# Peripherals.net
KiCad netlist of a schematic drawn in Altium Designer
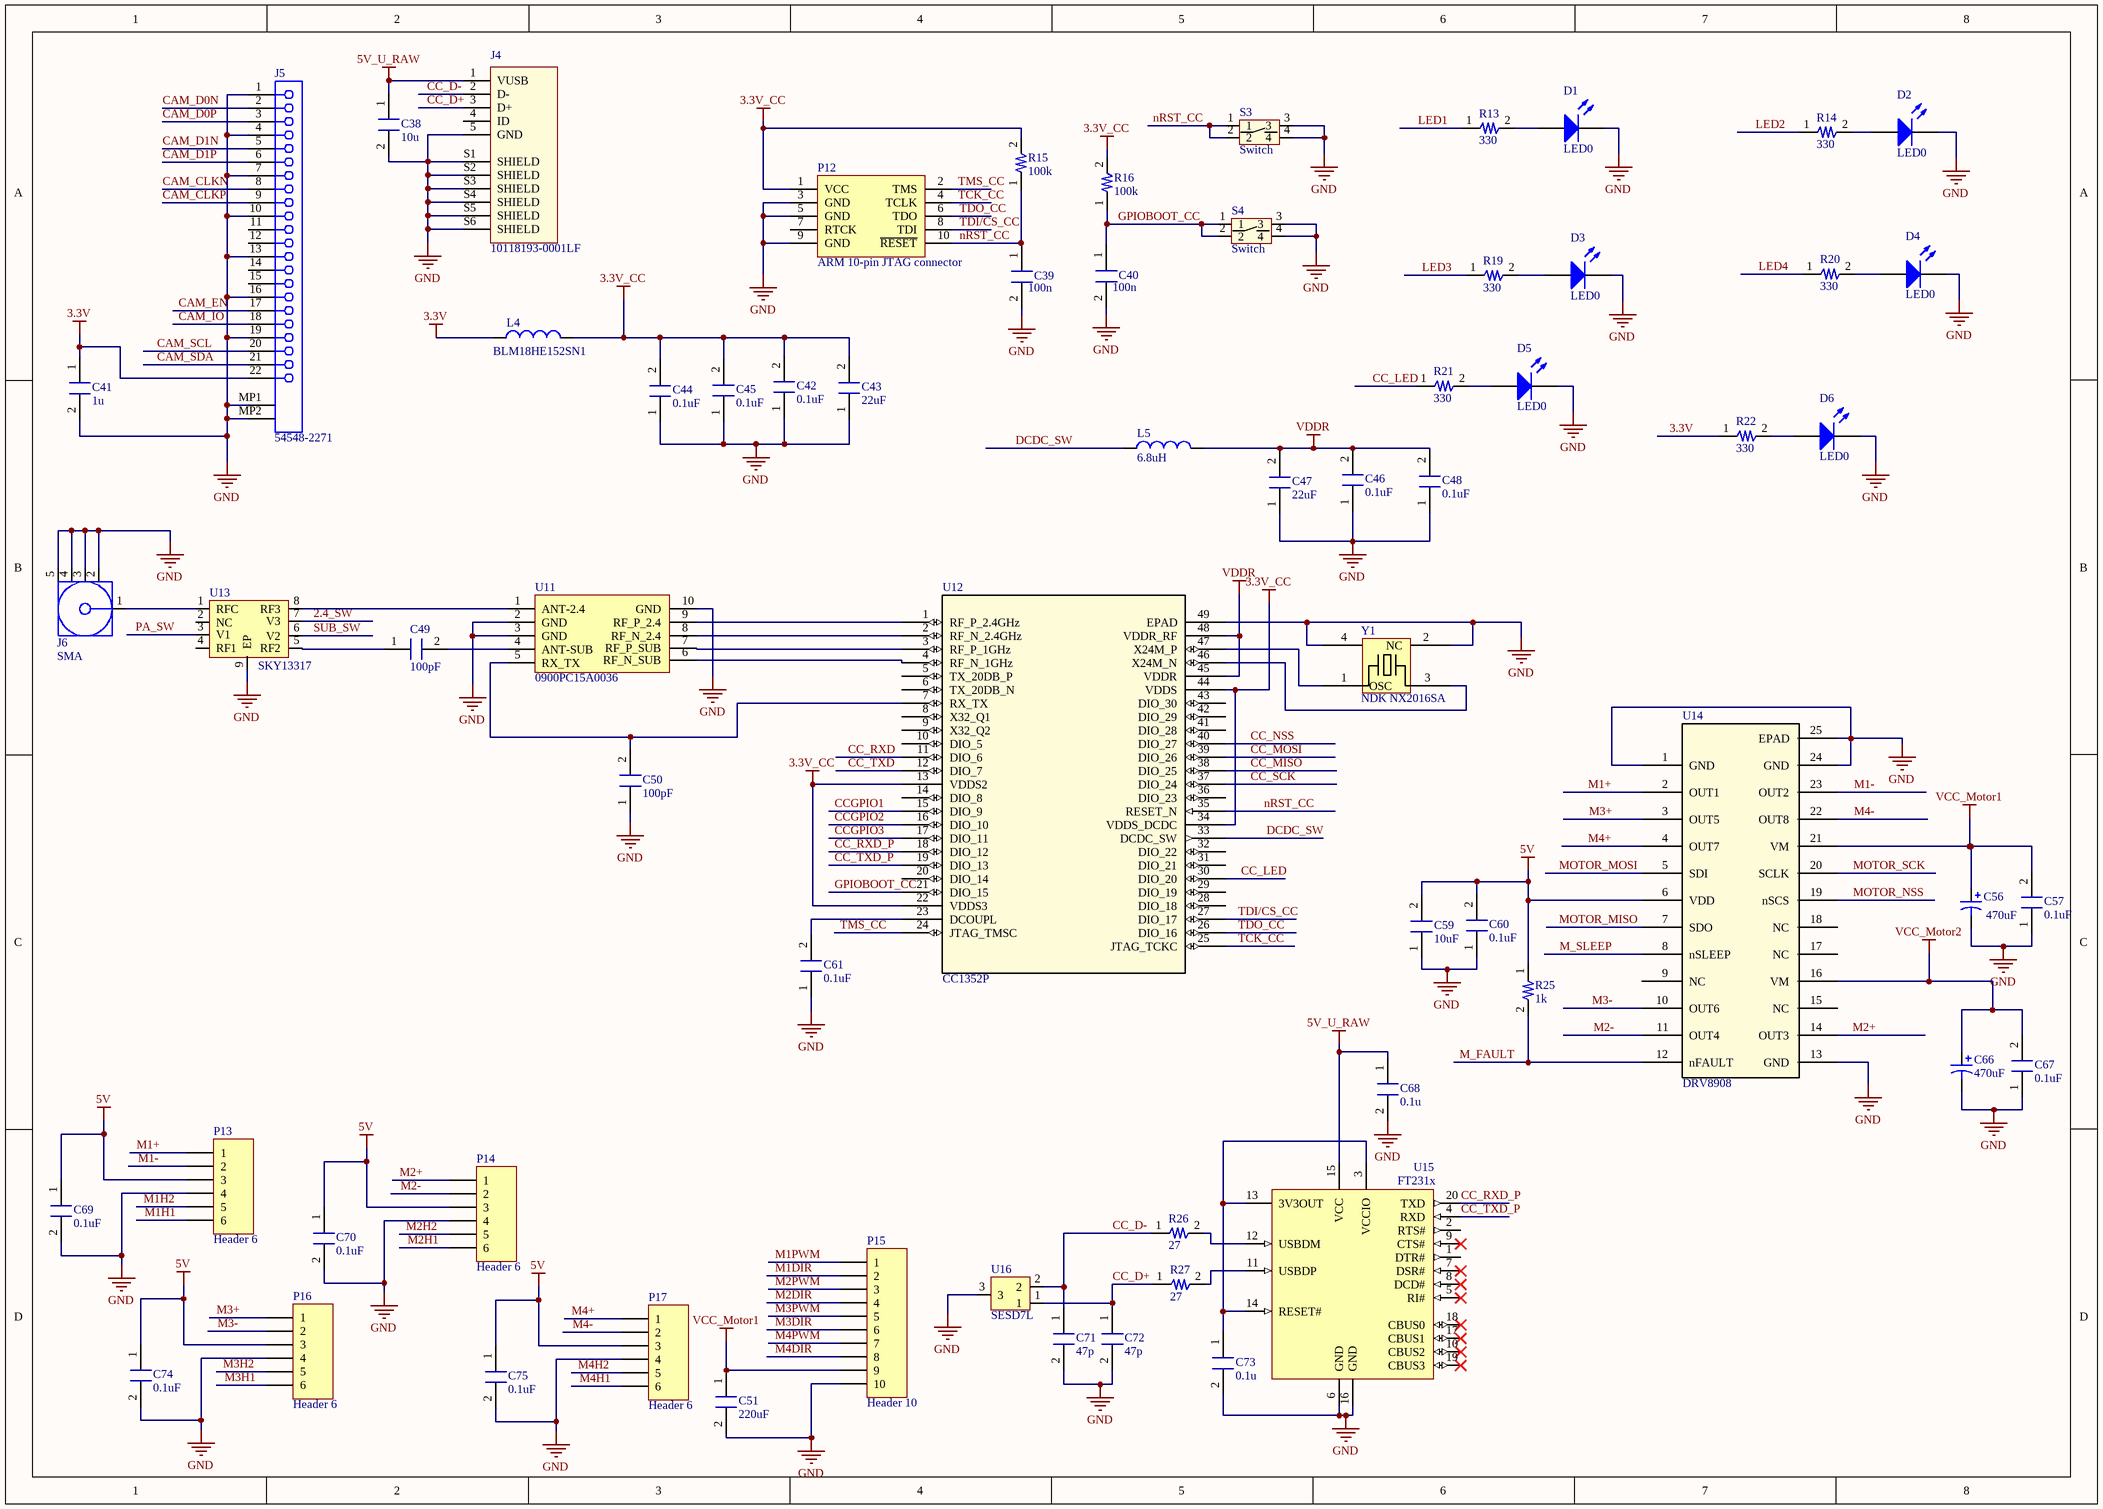
[diagram p0: Peripherals.SchDoc]

(export (version "E")
  (design (tool "Eeschema 10.0.6"))
  (components
    (comp (ref "C38")
      (value "10u")
      (footprint "Capacitor 0603")
      (fields (field (name "Comment") "Ceramic Capacitor"))
      (libsource (lib "Custom") (part "Ceramic Capacitor"))
    )
    (comp (ref "C39")
      (value "100n")
      (footprint "Capacitor 0402")
      (fields (field (name "Comment") "Ceramic Capacitor"))
      (libsource (lib "Custom") (part "Ceramic Capacitor"))
    )
    (comp (ref "C40")
      (value "100n")
      (footprint "Capacitor 0402")
      (fields (field (name "Comment") "Ceramic Capacitor"))
      (libsource (lib "Custom") (part "Ceramic Capacitor"))
    )
    (comp (ref "C41")
      (value "1u")
      (footprint "Capacitor 0402")
      (fields (field (name "Comment") "Ceramic Capacitor"))
      (libsource (lib "Custom") (part "Ceramic Capacitor"))
    )
    (comp (ref "C42")
      (value "0.1uF")
      (footprint "Capacitor 0402")
      (fields (field (name "Comment") "Ceramic Capacitor"))
      (libsource (lib "Custom") (part "Ceramic Capacitor"))
    )
    (comp (ref "C43")
      (value "22uF")
      (footprint "Capacitor 0603")
      (fields (field (name "Comment") "Ceramic Capacitor"))
      (libsource (lib "Custom") (part "Ceramic Capacitor"))
    )
    (comp (ref "C44")
      (value "0.1uF")
      (footprint "Capacitor 0402")
      (fields (field (name "Comment") "Ceramic Capacitor"))
      (libsource (lib "Custom") (part "Ceramic Capacitor"))
    )
    (comp (ref "C45")
      (value "0.1uF")
      (footprint "Capacitor 0402")
      (fields (field (name "Comment") "Ceramic Capacitor"))
      (libsource (lib "Custom") (part "Ceramic Capacitor"))
    )
    (comp (ref "C46")
      (value "0.1uF")
      (footprint "Capacitor 0402")
      (fields (field (name "Comment") "Ceramic Capacitor"))
      (libsource (lib "Custom") (part "Ceramic Capacitor"))
    )
    (comp (ref "C47")
      (value "22uF")
      (footprint "Capacitor 0603")
      (fields (field (name "Comment") "Ceramic Capacitor"))
      (libsource (lib "Custom") (part "Ceramic Capacitor"))
    )
    (comp (ref "C48")
      (value "0.1uF")
      (footprint "Capacitor 0402")
      (fields (field (name "Comment") "Ceramic Capacitor"))
      (libsource (lib "Custom") (part "Ceramic Capacitor"))
    )
    (comp (ref "C49")
      (value "100pF")
      (footprint "Capacitor 0402")
      (fields (field (name "Comment") "Ceramic Capacitor"))
      (libsource (lib "Custom") (part "Ceramic Capacitor"))
    )
    (comp (ref "C50")
      (value "100pF")
      (footprint "Capacitor 0402")
      (fields (field (name "Comment") "Ceramic Capacitor"))
      (libsource (lib "Custom") (part "Ceramic Capacitor"))
    )
    (comp (ref "C51")
      (value "220uF")
      (footprint "CAPAE250P680X1220_VERT")
      (fields (field (name "Comment") "Ceramic Capacitor"))
      (libsource (lib "Custom") (part "Ceramic Capacitor"))
    )
    (comp (ref "C56")
      (value "470uF")
      (footprint "RB7.6-15")
      (description "Polarized Capacitor (Radial)")
      (fields (field (name "PUBLISHER") "Altium Limited"))
      (libsource (lib "Miscellaneous Devices") (part "Cap Pol1"))
    )
    (comp (ref "C57")
      (value "0.1uF")
      (footprint "Capacitor 0402")
      (fields (field (name "Comment") "Ceramic Capacitor"))
      (libsource (lib "Custom") (part "Ceramic Capacitor"))
    )
    (comp (ref "C59")
      (value "10uF")
      (footprint "Capacitor 0603")
      (fields (field (name "Comment") "Ceramic Capacitor"))
      (libsource (lib "Custom") (part "Ceramic Capacitor"))
    )
    (comp (ref "C60")
      (value "0.1uF")
      (footprint "Capacitor 0402")
      (fields (field (name "Comment") "Ceramic Capacitor"))
      (libsource (lib "Custom") (part "Ceramic Capacitor"))
    )
    (comp (ref "C61")
      (value "0.1uF")
      (footprint "Capacitor 0402")
      (fields (field (name "Comment") "Ceramic Capacitor"))
      (libsource (lib "Custom") (part "Ceramic Capacitor"))
    )
    (comp (ref "C66")
      (value "470uF")
      (footprint "RB7.6-15")
      (description "Polarized Capacitor (Radial)")
      (fields (field (name "PUBLISHER") "Altium Limited"))
      (libsource (lib "Miscellaneous Devices") (part "Cap Pol1"))
    )
    (comp (ref "C67")
      (value "0.1uF")
      (footprint "Capacitor 0402")
      (fields (field (name "Comment") "Ceramic Capacitor"))
      (libsource (lib "Custom") (part "Ceramic Capacitor"))
    )
    (comp (ref "C68")
      (value "0.1u")
      (footprint "Capacitor 0402")
      (fields (field (name "Comment") "Ceramic Capacitor"))
      (libsource (lib "Custom") (part "Ceramic Capacitor"))
    )
    (comp (ref "C69")
      (value "0.1uF")
      (footprint "Capacitor 0402")
      (fields (field (name "Comment") "Ceramic Capacitor"))
      (libsource (lib "Custom") (part "Ceramic Capacitor"))
    )
    (comp (ref "C70")
      (value "0.1uF")
      (footprint "Capacitor 0402")
      (fields (field (name "Comment") "Ceramic Capacitor"))
      (libsource (lib "Custom") (part "Ceramic Capacitor"))
    )
    (comp (ref "C71")
      (value "47p")
      (footprint "Capacitor 0402")
      (fields (field (name "Comment") "Ceramic Capacitor"))
      (libsource (lib "Custom") (part "Ceramic Capacitor"))
    )
    (comp (ref "C72")
      (value "47p")
      (footprint "Capacitor 0402")
      (fields (field (name "Comment") "Ceramic Capacitor"))
      (libsource (lib "Custom") (part "Ceramic Capacitor"))
    )
    (comp (ref "C73")
      (value "0.1u")
      (footprint "Capacitor 0402")
      (fields (field (name "Comment") "Ceramic Capacitor"))
      (libsource (lib "Custom") (part "Ceramic Capacitor"))
    )
    (comp (ref "C74")
      (value "0.1uF")
      (footprint "Capacitor 0402")
      (fields (field (name "Comment") "Ceramic Capacitor"))
      (libsource (lib "Custom") (part "Ceramic Capacitor"))
    )
    (comp (ref "C75")
      (value "0.1uF")
      (footprint "Capacitor 0402")
      (fields (field (name "Comment") "Ceramic Capacitor"))
      (libsource (lib "Custom") (part "Ceramic Capacitor"))
    )
    (comp (ref "D1")
      (value "LED0")
      (footprint "HDR1X2")
      (description "Typical INFRARED GaAs LED")
      (fields (field (name "PUBLISHER") "Altium Limited"))
      (libsource (lib "Miscellaneous Devices") (part "LED0"))
    )
    (comp (ref "D2")
      (value "LED0")
      (footprint "HDR1X2")
      (description "Typical INFRARED GaAs LED")
      (fields (field (name "PUBLISHER") "Altium Limited"))
      (libsource (lib "Miscellaneous Devices") (part "LED0"))
    )
    (comp (ref "D3")
      (value "LED0")
      (footprint "HDR1X2")
      (description "Typical INFRARED GaAs LED")
      (fields (field (name "PUBLISHER") "Altium Limited"))
      (libsource (lib "Miscellaneous Devices") (part "LED0"))
    )
    (comp (ref "D4")
      (value "LED0")
      (footprint "HDR1X2")
      (description "Typical INFRARED GaAs LED")
      (fields (field (name "PUBLISHER") "Altium Limited"))
      (libsource (lib "Miscellaneous Devices") (part "LED0"))
    )
    (comp (ref "D5")
      (value "LED0")
      (footprint "HDR1X2")
      (description "Typical INFRARED GaAs LED")
      (fields (field (name "PUBLISHER") "Altium Limited"))
      (libsource (lib "Miscellaneous Devices") (part "LED0"))
    )
    (comp (ref "D6")
      (value "LED0")
      (footprint "HDR1X2")
      (description "Typical INFRARED GaAs LED")
      (fields (field (name "PUBLISHER") "Altium Limited"))
      (libsource (lib "Miscellaneous Devices") (part "LED0"))
    )
    (comp (ref "J4")
      (value "10118193-0001LF")
      (footprint "FCI_10118193-0001LF_10118193-0001LF(Primary)")
      (description "USB mini")
      (libsource (lib "Custom") (part "USB mini 10118193-0001LF"))
    )
    (comp (ref "J5")
      (value "54548-2271")
      (footprint "54548-2271")
      (libsource (lib "Custom") (part "54548-2271"))
    )
    (comp (ref "J6")
      (value "SMA")
      (footprint "SMA4.75V5A - Straight")
      (libsource (lib "Custom") (part "SMA"))
    )
    (comp (ref "L4")
      (value "BLM18HE152SN1")
      (footprint "Resistor 0603")
      (description "Inductor")
      (libsource (lib "Custom") (part "Inductor"))
    )
    (comp (ref "L5")
      (value "6.8uH")
      (footprint "B82144F2682K000")
      (description "Inductor")
      (fields (field (name "PART NUMBER") "B82144F2682K000"))
      (libsource (lib "Custom") (part "Inductor"))
    )
    (comp (ref "P12")
      (value "ARM 10-pin JTAG connector")
      (footprint "MHDR2X5")
      (description "ARM JTAG/SWD connector")
      (libsource (lib "Custom") (part "ARM JTAG"))
    )
    (comp (ref "P13")
      (value "Header 6")
      (footprint "HDR1X6")
      (description "Header, 6-Pin")
      (fields (field (name "PUBLISHER") "Altium Limited"))
      (libsource (lib "Miscellaneous Connectors") (part "Header 6"))
    )
    (comp (ref "P14")
      (value "Header 6")
      (footprint "HDR1X6")
      (description "Header, 6-Pin")
      (fields (field (name "PUBLISHER") "Altium Limited"))
      (libsource (lib "Miscellaneous Connectors") (part "Header 6"))
    )
    (comp (ref "P15")
      (value "Header 10")
      (footprint "HDR1X10")
      (description "Header, 10-Pin")
      (fields (field (name "PUBLISHER") "Altium Limited"))
      (libsource (lib "Miscellaneous Connectors") (part "Header 10"))
    )
    (comp (ref "P16")
      (value "Header 6")
      (footprint "HDR1X6")
      (description "Header, 6-Pin")
      (fields (field (name "PUBLISHER") "Altium Limited"))
      (libsource (lib "Miscellaneous Connectors") (part "Header 6"))
    )
    (comp (ref "P17")
      (value "Header 6")
      (footprint "HDR1X6")
      (description "Header, 6-Pin")
      (fields (field (name "PUBLISHER") "Altium Limited"))
      (libsource (lib "Miscellaneous Connectors") (part "Header 6"))
    )
    (comp (ref "R13")
      (value "330")
      (footprint "Resistor 0402")
      (description "General Purpose Resistor")
      (fields (field (name "Comment") "Resistor"))
      (libsource (lib "Custom") (part "Resistor"))
    )
    (comp (ref "R14")
      (value "330")
      (footprint "Resistor 0402")
      (description "General Purpose Resistor")
      (fields (field (name "Comment") "Resistor"))
      (libsource (lib "Custom") (part "Resistor"))
    )
    (comp (ref "R15")
      (value "100k")
      (footprint "Resistor 0402")
      (description "General Purpose Resistor")
      (fields (field (name "Comment") "Resistor"))
      (libsource (lib "Custom") (part "Resistor"))
    )
    (comp (ref "R16")
      (value "100k")
      (footprint "Resistor 0402")
      (description "General Purpose Resistor")
      (fields (field (name "Comment") "Resistor"))
      (libsource (lib "Custom") (part "Resistor"))
    )
    (comp (ref "R19")
      (value "330")
      (footprint "Resistor 0402")
      (description "General Purpose Resistor")
      (fields (field (name "Comment") "Resistor"))
      (libsource (lib "Custom") (part "Resistor"))
    )
    (comp (ref "R20")
      (value "330")
      (footprint "Resistor 0402")
      (description "General Purpose Resistor")
      (fields (field (name "Comment") "Resistor"))
      (libsource (lib "Custom") (part "Resistor"))
    )
    (comp (ref "R21")
      (value "330")
      (footprint "Resistor 0402")
      (description "General Purpose Resistor")
      (fields (field (name "Comment") "Resistor"))
      (libsource (lib "Custom") (part "Resistor"))
    )
    (comp (ref "R22")
      (value "330")
      (footprint "Resistor 0402")
      (description "General Purpose Resistor")
      (fields (field (name "Comment") "Resistor"))
      (libsource (lib "Custom") (part "Resistor"))
    )
    (comp (ref "R25")
      (value "1k")
      (footprint "Resistor 0402")
      (description "General Purpose Resistor")
      (fields (field (name "Comment") "Resistor"))
      (libsource (lib "Custom") (part "Resistor"))
    )
    (comp (ref "R26")
      (value "27")
      (footprint "Resistor 0402")
      (description "General Purpose Resistor")
      (fields (field (name "Comment") "Resistor"))
      (libsource (lib "Custom") (part "Resistor"))
    )
    (comp (ref "R27")
      (value "27")
      (footprint "Resistor 0402")
      (description "General Purpose Resistor")
      (fields (field (name "Comment") "Resistor"))
      (libsource (lib "Custom") (part "Resistor"))
    )
    (comp (ref "S3") (value "Switch") (footprint "Switch") (libsource (lib "Custom") (part "Switch")))
    (comp (ref "S4") (value "Switch") (footprint "Switch") (libsource (lib "Custom") (part "Switch")))
    (comp (ref "U11")
      (value "0900PC15A0036")
      (footprint "0900PC15A0036")
      (libsource (lib "Custom") (part "0900PC15A0036"))
    )
    (comp (ref "U12")
      (value "CC1352P")
      (footprint "RGZ48")
      (description "No Description Available")
      (libsource (lib "Custom") (part "CC1352P"))
    )
    (comp (ref "U13") (value "SKY13317") (footprint "DFN-8_DC") (libsource (lib "Custom") (part "SKY13317")))
    (comp (ref "U14")
      (value "DRV8908")
      (footprint "HTTSOP 24")
      (description "No Description Available")
      (libsource (lib "Custom") (part "DRV8908"))
    )
    (comp (ref "U15") (value "FT231x") (footprint "SSOP-20_N") (libsource (lib "Custom") (part "FT231x")))
    (comp (ref "U16")
      (value "SESD7L")
      (footprint "SOT-723")
      (description "TVS Diode - USB")
      (libsource (lib "Custom") (part "SESD7L"))
    )
    (comp (ref "Y1")
      (value "NDK NX2016SA")
      (footprint "NDK NX2016SA")
      (libsource (lib "Custom") (part "NDK NX2016SA"))
    )
  )
  (nets
    (net (code "1") (name "/2.4_SW") (class "Default")
      (node (ref "U13") (pin "7") (pinfunction "V3_7") (pintype "passive"))
    )
    (net (code "2") (name "/CAM_CLKN") (class "Default")
      (node (ref "J5") (pin "8") (pinfunction "8_8") (pintype "passive"))
    )
    (net (code "3") (name "/CAM_CLKP") (class "Default")
      (node (ref "J5") (pin "9") (pinfunction "9_9") (pintype "passive"))
    )
    (net (code "4") (name "/CAM_D0N") (class "Default")
      (node (ref "J5") (pin "2") (pinfunction "2_2") (pintype "passive"))
    )
    (net (code "5") (name "/CAM_D0P") (class "Default")
      (node (ref "J5") (pin "3") (pinfunction "3_3") (pintype "passive"))
    )
    (net (code "6") (name "/CAM_D1N") (class "Default")
      (node (ref "J5") (pin "5") (pinfunction "5_5") (pintype "passive"))
    )
    (net (code "7") (name "/CAM_D1P") (class "Default")
      (node (ref "J5") (pin "6") (pinfunction "6_6") (pintype "passive"))
    )
    (net (code "8") (name "/CAM_EN") (class "Default")
      (node (ref "J5") (pin "17") (pinfunction "17_17") (pintype "passive"))
    )
    (net (code "9") (name "/CAM_IO") (class "Default")
      (node (ref "J5") (pin "18") (pinfunction "18_18") (pintype "passive"))
    )
    (net (code "10") (name "/CAM_SCL") (class "Default")
      (node (ref "J5") (pin "20") (pinfunction "20_20") (pintype "passive"))
    )
    (net (code "11") (name "/CAM_SDA") (class "Default")
      (node (ref "J5") (pin "21") (pinfunction "21_21") (pintype "passive"))
    )
    (net (code "12") (name "/CCGPIO1") (class "Default")
      (node (ref "U12") (pin "15") (pinfunction "DIO_9_15") (pintype "bidirectional"))
    )
    (net (code "13") (name "/CCGPIO2") (class "Default")
      (node (ref "U12") (pin "16") (pinfunction "DIO_10_16") (pintype "bidirectional"))
    )
    (net (code "14") (name "/CCGPIO3") (class "Default")
      (node (ref "U12") (pin "17") (pinfunction "DIO_11_17") (pintype "bidirectional"))
    )
    (net (code "15") (name "/CC_D+") (class "Default")
      (node (ref "C72") (pin "1") (pinfunction "1_1") (pintype "passive"))
      (node (ref "J4") (pin "3") (pinfunction "D+_3") (pintype "passive"))
      (node (ref "R27") (pin "1") (pinfunction "1_1") (pintype "passive"))
      (node (ref "U16") (pin "1") (pinfunction "1_1") (pintype "passive"))
    )
    (net (code "16") (name "/CC_D-") (class "Default")
      (node (ref "C71") (pin "1") (pinfunction "1_1") (pintype "passive"))
      (node (ref "J4") (pin "2") (pinfunction "D-_2") (pintype "passive"))
      (node (ref "R26") (pin "1") (pinfunction "1_1") (pintype "passive"))
      (node (ref "U16") (pin "2") (pinfunction "2_2") (pintype "passive"))
    )
    (net (code "17") (name "/CC_LED") (class "Default")
      (node (ref "R21") (pin "1") (pinfunction "1_1") (pintype "passive"))
      (node (ref "U12") (pin "30") (pinfunction "DIO_20_30") (pintype "bidirectional"))
    )
    (net (code "18") (name "/CC_MISO") (class "Default")
      (node (ref "U12") (pin "38") (pinfunction "DIO_25_38") (pintype "bidirectional"))
    )
    (net (code "19") (name "/CC_MOSI") (class "Default")
      (node (ref "U12") (pin "39") (pinfunction "DIO_26_39") (pintype "bidirectional"))
    )
    (net (code "20") (name "/CC_NSS") (class "Default")
      (node (ref "U12") (pin "40") (pinfunction "DIO_27_40") (pintype "bidirectional"))
    )
    (net (code "21") (name "/CC_RXD") (class "Default")
      (node (ref "U12") (pin "11") (pinfunction "DIO_6_11") (pintype "bidirectional"))
    )
    (net (code "22") (name "/CC_RXD_P") (class "Default")
      (node (ref "U12") (pin "18") (pinfunction "DIO_12_18") (pintype "bidirectional"))
      (node (ref "U15") (pin "20") (pinfunction "TXD_20") (pintype "output"))
    )
    (net (code "23") (name "/CC_SCK") (class "Default")
      (node (ref "U12") (pin "37") (pinfunction "DIO_24_37") (pintype "bidirectional"))
    )
    (net (code "24") (name "/CC_TXD") (class "Default")
      (node (ref "U12") (pin "12") (pinfunction "DIO_7_12") (pintype "bidirectional"))
    )
    (net (code "25") (name "/CC_TXD_P") (class "Default")
      (node (ref "U12") (pin "19") (pinfunction "DIO_13_19") (pintype "bidirectional"))
      (node (ref "U15") (pin "4") (pinfunction "RXD_4") (pintype "input"))
    )
    (net (code "26") (name "/DCDC_SW") (class "Default")
      (node (ref "L5") (pin "1") (pinfunction "1_1") (pintype "passive"))
      (node (ref "U12") (pin "33") (pinfunction "DCDC_SW_33") (pintype "output"))
    )
    (net (code "27") (name "/GPIOBOOT_CC") (class "Default")
      (node (ref "C40") (pin "1") (pinfunction "1_1") (pintype "passive"))
      (node (ref "R16") (pin "1") (pinfunction "1_1") (pintype "passive"))
      (node (ref "S4") (pin "1") (pinfunction "1_1") (pintype "passive"))
      (node (ref "S4") (pin "2") (pinfunction "2_2") (pintype "passive"))
      (node (ref "U12") (pin "21") (pinfunction "DIO_15_21") (pintype "bidirectional"))
    )
    (net (code "28") (name "/LED1") (class "Default")
      (node (ref "R13") (pin "1") (pinfunction "1_1") (pintype "passive"))
    )
    (net (code "29") (name "/LED2") (class "Default")
      (node (ref "R14") (pin "1") (pinfunction "1_1") (pintype "passive"))
    )
    (net (code "30") (name "/LED3") (class "Default")
      (node (ref "R19") (pin "1") (pinfunction "1_1") (pintype "passive"))
    )
    (net (code "31") (name "/LED4") (class "Default")
      (node (ref "R20") (pin "1") (pinfunction "1_1") (pintype "passive"))
    )
    (net (code "32") (name "/M1+") (class "Default")
      (node (ref "P13") (pin "1") (pinfunction "1_1") (pintype "passive"))
      (node (ref "U14") (pin "2") (pinfunction "OUT1_2") (pintype "passive"))
    )
    (net (code "33") (name "/M1-") (class "Default")
      (node (ref "P13") (pin "2") (pinfunction "2_2") (pintype "passive"))
      (node (ref "U14") (pin "23") (pinfunction "OUT2_23") (pintype "passive"))
    )
    (net (code "34") (name "/M1DIR") (class "Default")
      (node (ref "P15") (pin "2") (pinfunction "2_2") (pintype "passive"))
    )
    (net (code "35") (name "/M1H1") (class "Default")
      (node (ref "P13") (pin "6") (pinfunction "6_6") (pintype "passive"))
    )
    (net (code "36") (name "/M1H2") (class "Default")
      (node (ref "P13") (pin "5") (pinfunction "5_5") (pintype "passive"))
    )
    (net (code "37") (name "/M1PWM") (class "Default")
      (node (ref "P15") (pin "1") (pinfunction "1_1") (pintype "passive"))
    )
    (net (code "38") (name "/M2+") (class "Default")
      (node (ref "P14") (pin "1") (pinfunction "1_1") (pintype "passive"))
      (node (ref "U14") (pin "14") (pinfunction "OUT3_14") (pintype "passive"))
    )
    (net (code "39") (name "/M2-") (class "Default")
      (node (ref "P14") (pin "2") (pinfunction "2_2") (pintype "passive"))
      (node (ref "U14") (pin "11") (pinfunction "OUT4_11") (pintype "passive"))
    )
    (net (code "40") (name "/M2DIR") (class "Default")
      (node (ref "P15") (pin "4") (pinfunction "4_4") (pintype "passive"))
    )
    (net (code "41") (name "/M2H1") (class "Default")
      (node (ref "P14") (pin "6") (pinfunction "6_6") (pintype "passive"))
    )
    (net (code "42") (name "/M2H2") (class "Default")
      (node (ref "P14") (pin "5") (pinfunction "5_5") (pintype "passive"))
    )
    (net (code "43") (name "/M2PWM") (class "Default")
      (node (ref "P15") (pin "3") (pinfunction "3_3") (pintype "passive"))
    )
    (net (code "44") (name "/M3+") (class "Default")
      (node (ref "P16") (pin "1") (pinfunction "1_1") (pintype "passive"))
      (node (ref "U14") (pin "3") (pinfunction "OUT5_3") (pintype "passive"))
    )
    (net (code "45") (name "/M3-") (class "Default")
      (node (ref "P16") (pin "2") (pinfunction "2_2") (pintype "passive"))
      (node (ref "U14") (pin "10") (pinfunction "OUT6_10") (pintype "passive"))
    )
    (net (code "46") (name "/M3DIR") (class "Default")
      (node (ref "P15") (pin "6") (pinfunction "6_6") (pintype "passive"))
    )
    (net (code "47") (name "/M3H1") (class "Default")
      (node (ref "P16") (pin "6") (pinfunction "6_6") (pintype "passive"))
    )
    (net (code "48") (name "/M3H2") (class "Default")
      (node (ref "P16") (pin "5") (pinfunction "5_5") (pintype "passive"))
    )
    (net (code "49") (name "/M3PWM") (class "Default")
      (node (ref "P15") (pin "5") (pinfunction "5_5") (pintype "passive"))
    )
    (net (code "50") (name "/M4+") (class "Default")
      (node (ref "P17") (pin "1") (pinfunction "1_1") (pintype "passive"))
      (node (ref "U14") (pin "4") (pinfunction "OUT7_4") (pintype "passive"))
    )
    (net (code "51") (name "/M4-") (class "Default")
      (node (ref "P17") (pin "2") (pinfunction "2_2") (pintype "passive"))
      (node (ref "U14") (pin "22") (pinfunction "OUT8_22") (pintype "passive"))
    )
    (net (code "52") (name "/M4DIR") (class "Default")
      (node (ref "P15") (pin "8") (pinfunction "8_8") (pintype "passive"))
    )
    (net (code "53") (name "/M4H1") (class "Default")
      (node (ref "P17") (pin "6") (pinfunction "6_6") (pintype "passive"))
    )
    (net (code "54") (name "/M4H2") (class "Default")
      (node (ref "P17") (pin "5") (pinfunction "5_5") (pintype "passive"))
    )
    (net (code "55") (name "/M4PWM") (class "Default")
      (node (ref "P15") (pin "7") (pinfunction "7_7") (pintype "passive"))
    )
    (net (code "56") (name "/MOTOR_MISO") (class "Default")
      (node (ref "U14") (pin "7") (pinfunction "SDO_7") (pintype "passive"))
    )
    (net (code "57") (name "/MOTOR_MOSI") (class "Default")
      (node (ref "U14") (pin "5") (pinfunction "SDI_5") (pintype "passive"))
    )
    (net (code "58") (name "/MOTOR_NSS") (class "Default")
      (node (ref "U14") (pin "19") (pinfunction "nSCS_19") (pintype "passive"))
    )
    (net (code "59") (name "/MOTOR_SCK") (class "Default")
      (node (ref "U14") (pin "20") (pinfunction "SCLK_20") (pintype "passive"))
    )
    (net (code "60") (name "/M_FAULT") (class "Default")
      (node (ref "R25") (pin "2") (pinfunction "2_2") (pintype "passive"))
      (node (ref "U14") (pin "12") (pinfunction "nFAULT_12") (pintype "passive"))
    )
    (net (code "61") (name "/M_SLEEP") (class "Default")
      (node (ref "U14") (pin "8") (pinfunction "nSLEEP_8") (pintype "passive"))
    )
    (net (code "62") (name "/PA_SW") (class "Default")
      (node (ref "U13") (pin "3") (pinfunction "V1_3") (pintype "passive"))
    )
    (net (code "63") (name "/SUB_SW") (class "Default")
      (node (ref "U13") (pin "6") (pinfunction "V2_6") (pintype "passive"))
    )
    (net (code "64") (name "/TCK_CC") (class "Default")
      (node (ref "P12") (pin "4") (pinfunction "TCLK_4") (pintype "passive"))
      (node (ref "U12") (pin "25") (pinfunction "JTAG_TCKC_25") (pintype "bidirectional"))
    )
    (net (code "65") (name "/TDI{slash}CS_CC") (class "Default")
      (node (ref "P12") (pin "8") (pinfunction "TDI_8") (pintype "passive"))
      (node (ref "U12") (pin "27") (pinfunction "DIO_17_27") (pintype "bidirectional"))
    )
    (net (code "66") (name "/TDO_CC") (class "Default")
      (node (ref "P12") (pin "6") (pinfunction "TDO_6") (pintype "passive"))
      (node (ref "U12") (pin "26") (pinfunction "DIO_16_26") (pintype "bidirectional"))
    )
    (net (code "67") (name "/TMS_CC") (class "Default")
      (node (ref "P12") (pin "2") (pinfunction "TMS_2") (pintype "passive"))
      (node (ref "U12") (pin "24") (pinfunction "JTAG_TMSC_24") (pintype "bidirectional"))
    )
    (net (code "68") (name "/nRST_CC") (class "Default")
      (node (ref "C39") (pin "1") (pinfunction "1_1") (pintype "passive"))
      (node (ref "P12") (pin "10") (pinfunction "~{RESET}_10") (pintype "passive"))
      (node (ref "R15") (pin "1") (pinfunction "1_1") (pintype "passive"))
      (node (ref "S3") (pin "1") (pinfunction "1_1") (pintype "passive"))
      (node (ref "S3") (pin "2") (pinfunction "2_2") (pintype "passive"))
      (node (ref "U12") (pin "35") (pinfunction "RESET_N_35") (pintype "input"))
    )
    (net (code "69") (name "3.3V") (class "Default")
      (node (ref "C41") (pin "1") (pinfunction "1_1") (pintype "passive"))
      (node (ref "J5") (pin "22") (pinfunction "22_22") (pintype "passive"))
      (node (ref "L4") (pin "1") (pinfunction "1_1") (pintype "passive"))
      (node (ref "R22") (pin "1") (pinfunction "1_1") (pintype "passive"))
    )
    (net (code "70") (name "3.3V_CC") (class "Default")
      (node (ref "C42") (pin "2") (pinfunction "2_2") (pintype "passive"))
      (node (ref "C43") (pin "2") (pinfunction "2_2") (pintype "passive"))
      (node (ref "C44") (pin "2") (pinfunction "2_2") (pintype "passive"))
      (node (ref "C45") (pin "2") (pinfunction "2_2") (pintype "passive"))
      (node (ref "L4") (pin "2") (pinfunction "2_2") (pintype "passive"))
      (node (ref "P12") (pin "1") (pinfunction "VCC_1") (pintype "passive"))
      (node (ref "R15") (pin "2") (pinfunction "2_2") (pintype "passive"))
      (node (ref "R16") (pin "2") (pinfunction "2_2") (pintype "passive"))
      (node (ref "U12") (pin "13") (pinfunction "VDDS2_13") (pintype "power_in"))
      (node (ref "U12") (pin "22") (pinfunction "VDDS3_22") (pintype "power_in"))
      (node (ref "U12") (pin "34") (pinfunction "VDDS_DCDC_34") (pintype "power_in"))
      (node (ref "U12") (pin "44") (pinfunction "VDDS_44") (pintype "power_in"))
    )
    (net (code "71") (name "5V") (class "Default")
      (node (ref "C59") (pin "2") (pinfunction "2_2") (pintype "passive"))
      (node (ref "C60") (pin "2") (pinfunction "2_2") (pintype "passive"))
      (node (ref "C69") (pin "1") (pinfunction "1_1") (pintype "passive"))
      (node (ref "C70") (pin "1") (pinfunction "1_1") (pintype "passive"))
      (node (ref "C74") (pin "1") (pinfunction "1_1") (pintype "passive"))
      (node (ref "C75") (pin "1") (pinfunction "1_1") (pintype "passive"))
      (node (ref "P13") (pin "3") (pinfunction "3_3") (pintype "passive"))
      (node (ref "P14") (pin "3") (pinfunction "3_3") (pintype "passive"))
      (node (ref "P16") (pin "3") (pinfunction "3_3") (pintype "passive"))
      (node (ref "P17") (pin "3") (pinfunction "3_3") (pintype "passive"))
      (node (ref "R25") (pin "1") (pinfunction "1_1") (pintype "passive"))
      (node (ref "U14") (pin "6") (pinfunction "VDD_6") (pintype "passive"))
    )
    (net (code "72") (name "5V_U_RAW") (class "Default")
      (node (ref "C38") (pin "1") (pinfunction "1_1") (pintype "passive"))
      (node (ref "C68") (pin "1") (pinfunction "1_1") (pintype "passive"))
      (node (ref "J4") (pin "1") (pinfunction "VUSB_1") (pintype "passive"))
      (node (ref "U15") (pin "15") (pinfunction "VCC_15") (pintype "power_in"))
    )
    (net (code "73") (name "GND") (class "Default")
      (node (ref "C38") (pin "2") (pinfunction "2_2") (pintype "passive"))
      (node (ref "C39") (pin "2") (pinfunction "2_2") (pintype "passive"))
      (node (ref "C40") (pin "2") (pinfunction "2_2") (pintype "passive"))
      (node (ref "C41") (pin "2") (pinfunction "2_2") (pintype "passive"))
      (node (ref "C42") (pin "1") (pinfunction "1_1") (pintype "passive"))
      (node (ref "C43") (pin "1") (pinfunction "1_1") (pintype "passive"))
      (node (ref "C44") (pin "1") (pinfunction "1_1") (pintype "passive"))
      (node (ref "C45") (pin "1") (pinfunction "1_1") (pintype "passive"))
      (node (ref "C46") (pin "1") (pinfunction "1_1") (pintype "passive"))
      (node (ref "C47") (pin "1") (pinfunction "1_1") (pintype "passive"))
      (node (ref "C48") (pin "1") (pinfunction "1_1") (pintype "passive"))
      (node (ref "C50") (pin "1") (pinfunction "1_1") (pintype "passive"))
      (node (ref "C51") (pin "2") (pinfunction "2_2") (pintype "passive"))
      (node (ref "C56") (pin "2") (pinfunction "2_2") (pintype "passive"))
      (node (ref "C57") (pin "1") (pinfunction "1_1") (pintype "passive"))
      (node (ref "C59") (pin "1") (pinfunction "1_1") (pintype "passive"))
      (node (ref "C60") (pin "1") (pinfunction "1_1") (pintype "passive"))
      (node (ref "C61") (pin "1") (pinfunction "1_1") (pintype "passive"))
      (node (ref "C66") (pin "2") (pinfunction "2_2") (pintype "passive"))
      (node (ref "C67") (pin "1") (pinfunction "1_1") (pintype "passive"))
      (node (ref "C68") (pin "2") (pinfunction "2_2") (pintype "passive"))
      (node (ref "C69") (pin "2") (pinfunction "2_2") (pintype "passive"))
      (node (ref "C70") (pin "2") (pinfunction "2_2") (pintype "passive"))
      (node (ref "C71") (pin "2") (pinfunction "2_2") (pintype "passive"))
      (node (ref "C72") (pin "2") (pinfunction "2_2") (pintype "passive"))
      (node (ref "C73") (pin "2") (pinfunction "2_2") (pintype "passive"))
      (node (ref "C74") (pin "2") (pinfunction "2_2") (pintype "passive"))
      (node (ref "C75") (pin "2") (pinfunction "2_2") (pintype "passive"))
      (node (ref "D1") (pin "2") (pinfunction "K_2") (pintype "passive"))
      (node (ref "D2") (pin "2") (pinfunction "K_2") (pintype "passive"))
      (node (ref "D3") (pin "2") (pinfunction "K_2") (pintype "passive"))
      (node (ref "D4") (pin "2") (pinfunction "K_2") (pintype "passive"))
      (node (ref "D5") (pin "2") (pinfunction "K_2") (pintype "passive"))
      (node (ref "D6") (pin "2") (pinfunction "K_2") (pintype "passive"))
      (node (ref "J4") (pin "5") (pinfunction "GND_5") (pintype "passive"))
      (node (ref "J4") (pin "S1") (pinfunction "SHIELD_S1") (pintype "passive"))
      (node (ref "J4") (pin "S2") (pinfunction "SHIELD_S2") (pintype "passive"))
      (node (ref "J4") (pin "S3") (pinfunction "SHIELD_S3") (pintype "passive"))
      (node (ref "J4") (pin "S4") (pinfunction "SHIELD_S4") (pintype "passive"))
      (node (ref "J4") (pin "S5") (pinfunction "SHIELD_S5") (pintype "passive"))
      (node (ref "J4") (pin "S6") (pinfunction "SHIELD_S6") (pintype "passive"))
      (node (ref "J5") (pin "1") (pinfunction "1_1") (pintype "passive"))
      (node (ref "J5") (pin "10") (pinfunction "10_10") (pintype "passive"))
      (node (ref "J5") (pin "13") (pinfunction "13_13") (pintype "passive"))
      (node (ref "J5") (pin "16") (pinfunction "16_16") (pintype "passive"))
      (node (ref "J5") (pin "19") (pinfunction "19_19") (pintype "passive"))
      (node (ref "J5") (pin "4") (pinfunction "4_4") (pintype "passive"))
      (node (ref "J5") (pin "7") (pinfunction "7_7") (pintype "passive"))
      (node (ref "J5") (pin "MP1") (pinfunction "MP1_MP1") (pintype "passive"))
      (node (ref "J5") (pin "MP2") (pinfunction "MP2_MP2") (pintype "passive"))
      (node (ref "J6") (pin "2") (pinfunction "2_2") (pintype "passive"))
      (node (ref "J6") (pin "3") (pinfunction "3_3") (pintype "passive"))
      (node (ref "J6") (pin "4") (pinfunction "4_4") (pintype "passive"))
      (node (ref "J6") (pin "5") (pinfunction "5_5") (pintype "passive"))
      (node (ref "P12") (pin "3") (pinfunction "GND_3") (pintype "passive"))
      (node (ref "P12") (pin "5") (pinfunction "GND_5") (pintype "passive"))
      (node (ref "P12") (pin "9") (pinfunction "GND_9") (pintype "passive"))
      (node (ref "P13") (pin "4") (pinfunction "4_4") (pintype "passive"))
      (node (ref "P14") (pin "4") (pinfunction "4_4") (pintype "passive"))
      (node (ref "P15") (pin "10") (pinfunction "10_10") (pintype "passive"))
      (node (ref "P16") (pin "4") (pinfunction "4_4") (pintype "passive"))
      (node (ref "P17") (pin "4") (pinfunction "4_4") (pintype "passive"))
      (node (ref "S3") (pin "3") (pinfunction "3_3") (pintype "passive"))
      (node (ref "S3") (pin "4") (pinfunction "4_4") (pintype "passive"))
      (node (ref "S4") (pin "3") (pinfunction "3_3") (pintype "passive"))
      (node (ref "S4") (pin "4") (pinfunction "4_4") (pintype "passive"))
      (node (ref "U11") (pin "10") (pinfunction "GND_10") (pintype "power_in"))
      (node (ref "U11") (pin "2") (pinfunction "GND_2") (pintype "passive"))
      (node (ref "U11") (pin "3") (pinfunction "GND_3") (pintype "passive"))
      (node (ref "U12") (pin "49") (pinfunction "EPAD_49") (pintype "passive"))
      (node (ref "U13") (pin "9") (pinfunction "EP_9") (pintype "passive"))
      (node (ref "U14") (pin "1") (pinfunction "GND_1") (pintype "passive"))
      (node (ref "U14") (pin "13") (pinfunction "GND_13") (pintype "passive"))
      (node (ref "U14") (pin "24") (pinfunction "GND_24") (pintype "passive"))
      (node (ref "U14") (pin "25") (pinfunction "EPAD_25") (pintype "passive"))
      (node (ref "U15") (pin "16") (pinfunction "GND_16") (pintype "power_in"))
      (node (ref "U15") (pin "6") (pinfunction "GND_6") (pintype "power_in"))
      (node (ref "U16") (pin "3") (pinfunction "3_3") (pintype "passive"))
      (node (ref "Y1") (pin "2") (pinfunction "NC_2") (pintype "passive"))
      (node (ref "Y1") (pin "4") (pinfunction "NC_4") (pintype "passive"))
    )
    (net (code "74") (name "Net-(D1-A)") (class "Default")
      (node (ref "D1") (pin "1") (pinfunction "A_1") (pintype "passive"))
      (node (ref "R13") (pin "2") (pinfunction "2_2") (pintype "passive"))
    )
    (net (code "75") (name "Net-(D2-A)") (class "Default")
      (node (ref "D2") (pin "1") (pinfunction "A_1") (pintype "passive"))
      (node (ref "R14") (pin "2") (pinfunction "2_2") (pintype "passive"))
    )
    (net (code "76") (name "Net-(D3-A)") (class "Default")
      (node (ref "D3") (pin "1") (pinfunction "A_1") (pintype "passive"))
      (node (ref "R19") (pin "2") (pinfunction "2_2") (pintype "passive"))
    )
    (net (code "77") (name "Net-(D4-A)") (class "Default")
      (node (ref "D4") (pin "1") (pinfunction "A_1") (pintype "passive"))
      (node (ref "R20") (pin "2") (pinfunction "2_2") (pintype "passive"))
    )
    (net (code "78") (name "Net-(D5-A)") (class "Default")
      (node (ref "D5") (pin "1") (pinfunction "A_1") (pintype "passive"))
      (node (ref "R21") (pin "2") (pinfunction "2_2") (pintype "passive"))
    )
    (net (code "79") (name "Net-(D6-A)") (class "Default")
      (node (ref "D6") (pin "1") (pinfunction "A_1") (pintype "passive"))
      (node (ref "R22") (pin "2") (pinfunction "2_2") (pintype "passive"))
    )
    (net (code "80") (name "Net-(U11-ANT-2.4)") (class "Default")
      (node (ref "U11") (pin "1") (pinfunction "ANT-2.4_1") (pintype "passive"))
      (node (ref "U13") (pin "8") (pinfunction "RF3_8") (pintype "passive"))
    )
    (net (code "81") (name "Net-(U11-ANT-SUB)") (class "Default")
      (node (ref "C49") (pin "2") (pinfunction "2_2") (pintype "passive"))
      (node (ref "U11") (pin "4") (pinfunction "ANT-SUB_4") (pintype "power_in"))
    )
    (net (code "82") (name "Net-(U11-RF_N_2.4)") (class "Default")
      (node (ref "U11") (pin "8") (pinfunction "RF_N_2.4_8") (pintype "power_in"))
      (node (ref "U12") (pin "2") (pinfunction "RF_N_2.4GHz_2") (pintype "bidirectional"))
    )
    (net (code "83") (name "Net-(U11-RF_N_SUB)") (class "Default")
      (node (ref "U11") (pin "6") (pinfunction "RF_N_SUB_6") (pintype "power_in"))
      (node (ref "U12") (pin "4") (pinfunction "RF_N_1GHz_4") (pintype "bidirectional"))
    )
    (net (code "84") (name "Net-(U11-RF_P_2.4)") (class "Default")
      (node (ref "U11") (pin "9") (pinfunction "RF_P_2.4_9") (pintype "power_in"))
      (node (ref "U12") (pin "1") (pinfunction "RF_P_2.4GHz_1") (pintype "bidirectional"))
    )
    (net (code "85") (name "Net-(U11-RF_P_SUB)") (class "Default")
      (node (ref "U11") (pin "7") (pinfunction "RF_P_SUB_7") (pintype "power_in"))
      (node (ref "U12") (pin "3") (pinfunction "RF_P_1GHz_3") (pintype "bidirectional"))
    )
    (net (code "86") (name "Net-(U11-RX_TX)") (class "Default")
      (node (ref "C50") (pin "2") (pinfunction "2_2") (pintype "passive"))
      (node (ref "U11") (pin "5") (pinfunction "RX_TX_5") (pintype "power_in"))
      (node (ref "U12") (pin "7") (pinfunction "RX_TX_7") (pintype "bidirectional"))
    )
    (net (code "87") (name "Net-(U12-DCOUPL)") (class "Default")
      (node (ref "C61") (pin "2") (pinfunction "2_2") (pintype "passive"))
      (node (ref "U12") (pin "23") (pinfunction "DCOUPL_23") (pintype "passive"))
    )
    (net (code "88") (name "Net-(U12-X24M_N)") (class "Default")
      (node (ref "U12") (pin "46") (pinfunction "X24M_N_46") (pintype "bidirectional"))
      (node (ref "Y1") (pin "3") (pinfunction "OSC_3") (pintype "passive"))
    )
    (net (code "89") (name "Net-(U12-X24M_P)") (class "Default")
      (node (ref "U12") (pin "47") (pinfunction "X24M_P_47") (pintype "bidirectional"))
      (node (ref "Y1") (pin "1") (pinfunction "OSC_1") (pintype "passive"))
    )
    (net (code "90") (name "Net-(U13-RF2)") (class "Default")
      (node (ref "C49") (pin "1") (pinfunction "1_1") (pintype "passive"))
      (node (ref "U13") (pin "5") (pinfunction "RF2_5") (pintype "passive"))
    )
    (net (code "91") (name "Net-(U13-RFC)") (class "Default")
      (node (ref "J6") (pin "1") (pinfunction "1_1") (pintype "passive"))
      (node (ref "U13") (pin "1") (pinfunction "RFC_1") (pintype "passive"))
    )
    (net (code "92") (name "Net-(U15-3V3OUT)") (class "Default")
      (node (ref "C73") (pin "1") (pinfunction "1_1") (pintype "passive"))
      (node (ref "U15") (pin "13") (pinfunction "3V3OUT_13") (pintype "power_in"))
      (node (ref "U15") (pin "14") (pinfunction "RESET#_14") (pintype "input"))
      (node (ref "U15") (pin "3") (pinfunction "VCCIO_3") (pintype "power_in"))
    )
    (net (code "93") (name "Net-(U15-USBDM)") (class "Default")
      (node (ref "R26") (pin "2") (pinfunction "2_2") (pintype "passive"))
      (node (ref "U15") (pin "12") (pinfunction "USBDM_12") (pintype "input"))
    )
    (net (code "94") (name "Net-(U15-USBDP)") (class "Default")
      (node (ref "R27") (pin "2") (pinfunction "2_2") (pintype "passive"))
      (node (ref "U15") (pin "11") (pinfunction "USBDP_11") (pintype "input"))
    )
    (net (code "95") (name "VCC_Motor1") (class "Default")
      (node (ref "C51") (pin "1") (pinfunction "1_1") (pintype "passive"))
      (node (ref "C56") (pin "1") (pinfunction "1_1") (pintype "passive"))
      (node (ref "C57") (pin "2") (pinfunction "2_2") (pintype "passive"))
      (node (ref "P15") (pin "9") (pinfunction "9_9") (pintype "passive"))
      (node (ref "U14") (pin "21") (pinfunction "VM_21") (pintype "passive"))
    )
    (net (code "96") (name "VCC_Motor2") (class "Default")
      (node (ref "C66") (pin "1") (pinfunction "1_1") (pintype "passive"))
      (node (ref "C67") (pin "2") (pinfunction "2_2") (pintype "passive"))
      (node (ref "U14") (pin "16") (pinfunction "VM_16") (pintype "passive"))
    )
    (net (code "97") (name "VDDR") (class "Default")
      (node (ref "C46") (pin "2") (pinfunction "2_2") (pintype "passive"))
      (node (ref "C47") (pin "2") (pinfunction "2_2") (pintype "passive"))
      (node (ref "C48") (pin "2") (pinfunction "2_2") (pintype "passive"))
      (node (ref "L5") (pin "2") (pinfunction "2_2") (pintype "passive"))
      (node (ref "U12") (pin "45") (pinfunction "VDDR_45") (pintype "power_in"))
      (node (ref "U12") (pin "48") (pinfunction "VDDR_RF_48") (pintype "power_in"))
    )
    (net (code "98") (name "unconnected-(J4-ID-Pad4)") (class "Default")
      (node (ref "J4") (pin "4") (pinfunction "ID_4") (pintype "passive"))
    )
    (net (code "99") (name "unconnected-(J5-Pad11)") (class "Default")
      (node (ref "J5") (pin "11") (pinfunction "11_11") (pintype "passive"))
    )
    (net (code "100") (name "unconnected-(J5-Pad12)") (class "Default")
      (node (ref "J5") (pin "12") (pinfunction "12_12") (pintype "passive"))
    )
    (net (code "101") (name "unconnected-(J5-Pad14)") (class "Default")
      (node (ref "J5") (pin "14") (pinfunction "14_14") (pintype "passive"))
    )
    (net (code "102") (name "unconnected-(J5-Pad15)") (class "Default")
      (node (ref "J5") (pin "15") (pinfunction "15_15") (pintype "passive"))
    )
    (net (code "103") (name "unconnected-(P12-RTCK-Pad7)") (class "Default")
      (node (ref "P12") (pin "7") (pinfunction "RTCK_7") (pintype "passive"))
    )
    (net (code "104") (name "unconnected-(U12-DIO_5-Pad10)") (class "Default")
      (node (ref "U12") (pin "10") (pinfunction "DIO_5_10") (pintype "bidirectional"))
    )
    (net (code "105") (name "unconnected-(U12-DIO_8-Pad14)") (class "Default")
      (node (ref "U12") (pin "14") (pinfunction "DIO_8_14") (pintype "bidirectional"))
    )
    (net (code "106") (name "unconnected-(U12-DIO_14-Pad20)") (class "Default")
      (node (ref "U12") (pin "20") (pinfunction "DIO_14_20") (pintype "bidirectional"))
    )
    (net (code "107") (name "unconnected-(U12-DIO_18-Pad28)") (class "Default")
      (node (ref "U12") (pin "28") (pinfunction "DIO_18_28") (pintype "bidirectional"))
    )
    (net (code "108") (name "unconnected-(U12-DIO_19-Pad29)") (class "Default")
      (node (ref "U12") (pin "29") (pinfunction "DIO_19_29") (pintype "bidirectional"))
    )
    (net (code "109") (name "unconnected-(U12-DIO_21-Pad31)") (class "Default")
      (node (ref "U12") (pin "31") (pinfunction "DIO_21_31") (pintype "bidirectional"))
    )
    (net (code "110") (name "unconnected-(U12-DIO_22-Pad32)") (class "Default")
      (node (ref "U12") (pin "32") (pinfunction "DIO_22_32") (pintype "bidirectional"))
    )
    (net (code "111") (name "unconnected-(U12-DIO_23-Pad36)") (class "Default")
      (node (ref "U12") (pin "36") (pinfunction "DIO_23_36") (pintype "bidirectional"))
    )
    (net (code "112") (name "unconnected-(U12-DIO_28-Pad41)") (class "Default")
      (node (ref "U12") (pin "41") (pinfunction "DIO_28_41") (pintype "bidirectional"))
    )
    (net (code "113") (name "unconnected-(U12-DIO_29-Pad42)") (class "Default")
      (node (ref "U12") (pin "42") (pinfunction "DIO_29_42") (pintype "bidirectional"))
    )
    (net (code "114") (name "unconnected-(U12-DIO_30-Pad43)") (class "Default")
      (node (ref "U12") (pin "43") (pinfunction "DIO_30_43") (pintype "bidirectional"))
    )
    (net (code "115") (name "unconnected-(U12-TX_20DB_N-Pad6)") (class "Default")
      (node (ref "U12") (pin "6") (pinfunction "TX_20DB_N_6") (pintype "bidirectional"))
    )
    (net (code "116") (name "unconnected-(U12-TX_20DB_P-Pad5)") (class "Default")
      (node (ref "U12") (pin "5") (pinfunction "TX_20DB_P_5") (pintype "bidirectional"))
    )
    (net (code "117") (name "unconnected-(U12-X32_Q1-Pad8)") (class "Default")
      (node (ref "U12") (pin "8") (pinfunction "X32_Q1_8") (pintype "bidirectional"))
    )
    (net (code "118") (name "unconnected-(U12-X32_Q2-Pad9)") (class "Default")
      (node (ref "U12") (pin "9") (pinfunction "X32_Q2_9") (pintype "bidirectional"))
    )
    (net (code "119") (name "unconnected-(U13-NC-Pad2)") (class "Default")
      (node (ref "U13") (pin "2") (pinfunction "NC_2") (pintype "passive"))
    )
    (net (code "120") (name "unconnected-(U13-RF1-Pad4)") (class "Default")
      (node (ref "U13") (pin "4") (pinfunction "RF1_4") (pintype "passive"))
    )
    (net (code "121") (name "unconnected-(U14-NC-Pad9)") (class "Default")
      (node (ref "U14") (pin "9") (pinfunction "NC_9") (pintype "passive"))
    )
    (net (code "122") (name "unconnected-(U14-NC-Pad15)") (class "Default")
      (node (ref "U14") (pin "15") (pinfunction "NC_15") (pintype "passive"))
    )
    (net (code "123") (name "unconnected-(U14-NC-Pad17)") (class "Default")
      (node (ref "U14") (pin "17") (pinfunction "NC_17") (pintype "passive"))
    )
    (net (code "124") (name "unconnected-(U14-NC-Pad18)") (class "Default")
      (node (ref "U14") (pin "18") (pinfunction "NC_18") (pintype "passive"))
    )
    (net (code "125") (name "unconnected-(U15-CBUS0-Pad18)") (class "Default")
      (node (ref "U15") (pin "18") (pinfunction "CBUS0_18") (pintype "bidirectional+no_connect"))
    )
    (net (code "126") (name "unconnected-(U15-CBUS1-Pad17)") (class "Default")
      (node (ref "U15") (pin "17") (pinfunction "CBUS1_17") (pintype "bidirectional+no_connect"))
    )
    (net (code "127") (name "unconnected-(U15-CBUS2-Pad10)") (class "Default")
      (node (ref "U15") (pin "10") (pinfunction "CBUS2_10") (pintype "bidirectional+no_connect"))
    )
    (net (code "128") (name "unconnected-(U15-CBUS3-Pad19)") (class "Default")
      (node (ref "U15") (pin "19") (pinfunction "CBUS3_19") (pintype "bidirectional+no_connect"))
    )
    (net (code "129") (name "unconnected-(U15-CTS#-Pad9)") (class "Default")
      (node (ref "U15") (pin "9") (pinfunction "CTS#_9") (pintype "input+no_connect"))
    )
    (net (code "130") (name "unconnected-(U15-DCD#-Pad8)") (class "Default")
      (node (ref "U15") (pin "8") (pinfunction "DCD#_8") (pintype "input+no_connect"))
    )
    (net (code "131") (name "unconnected-(U15-DSR#-Pad7)") (class "Default")
      (node (ref "U15") (pin "7") (pinfunction "DSR#_7") (pintype "input+no_connect"))
    )
    (net (code "132") (name "unconnected-(U15-DTR#-Pad1)") (class "Default")
      (node (ref "U15") (pin "1") (pinfunction "DTR#_1") (pintype "output"))
    )
    (net (code "133") (name "unconnected-(U15-RI#-Pad5)") (class "Default")
      (node (ref "U15") (pin "5") (pinfunction "RI#_5") (pintype "input+no_connect"))
    )
    (net (code "134") (name "unconnected-(U15-RTS#-Pad2)") (class "Default")
      (node (ref "U15") (pin "2") (pinfunction "RTS#_2") (pintype "output"))
    )
  )
)
